# EE209_Schematic.net
KiCad netlist of a schematic drawn in Altium Designer
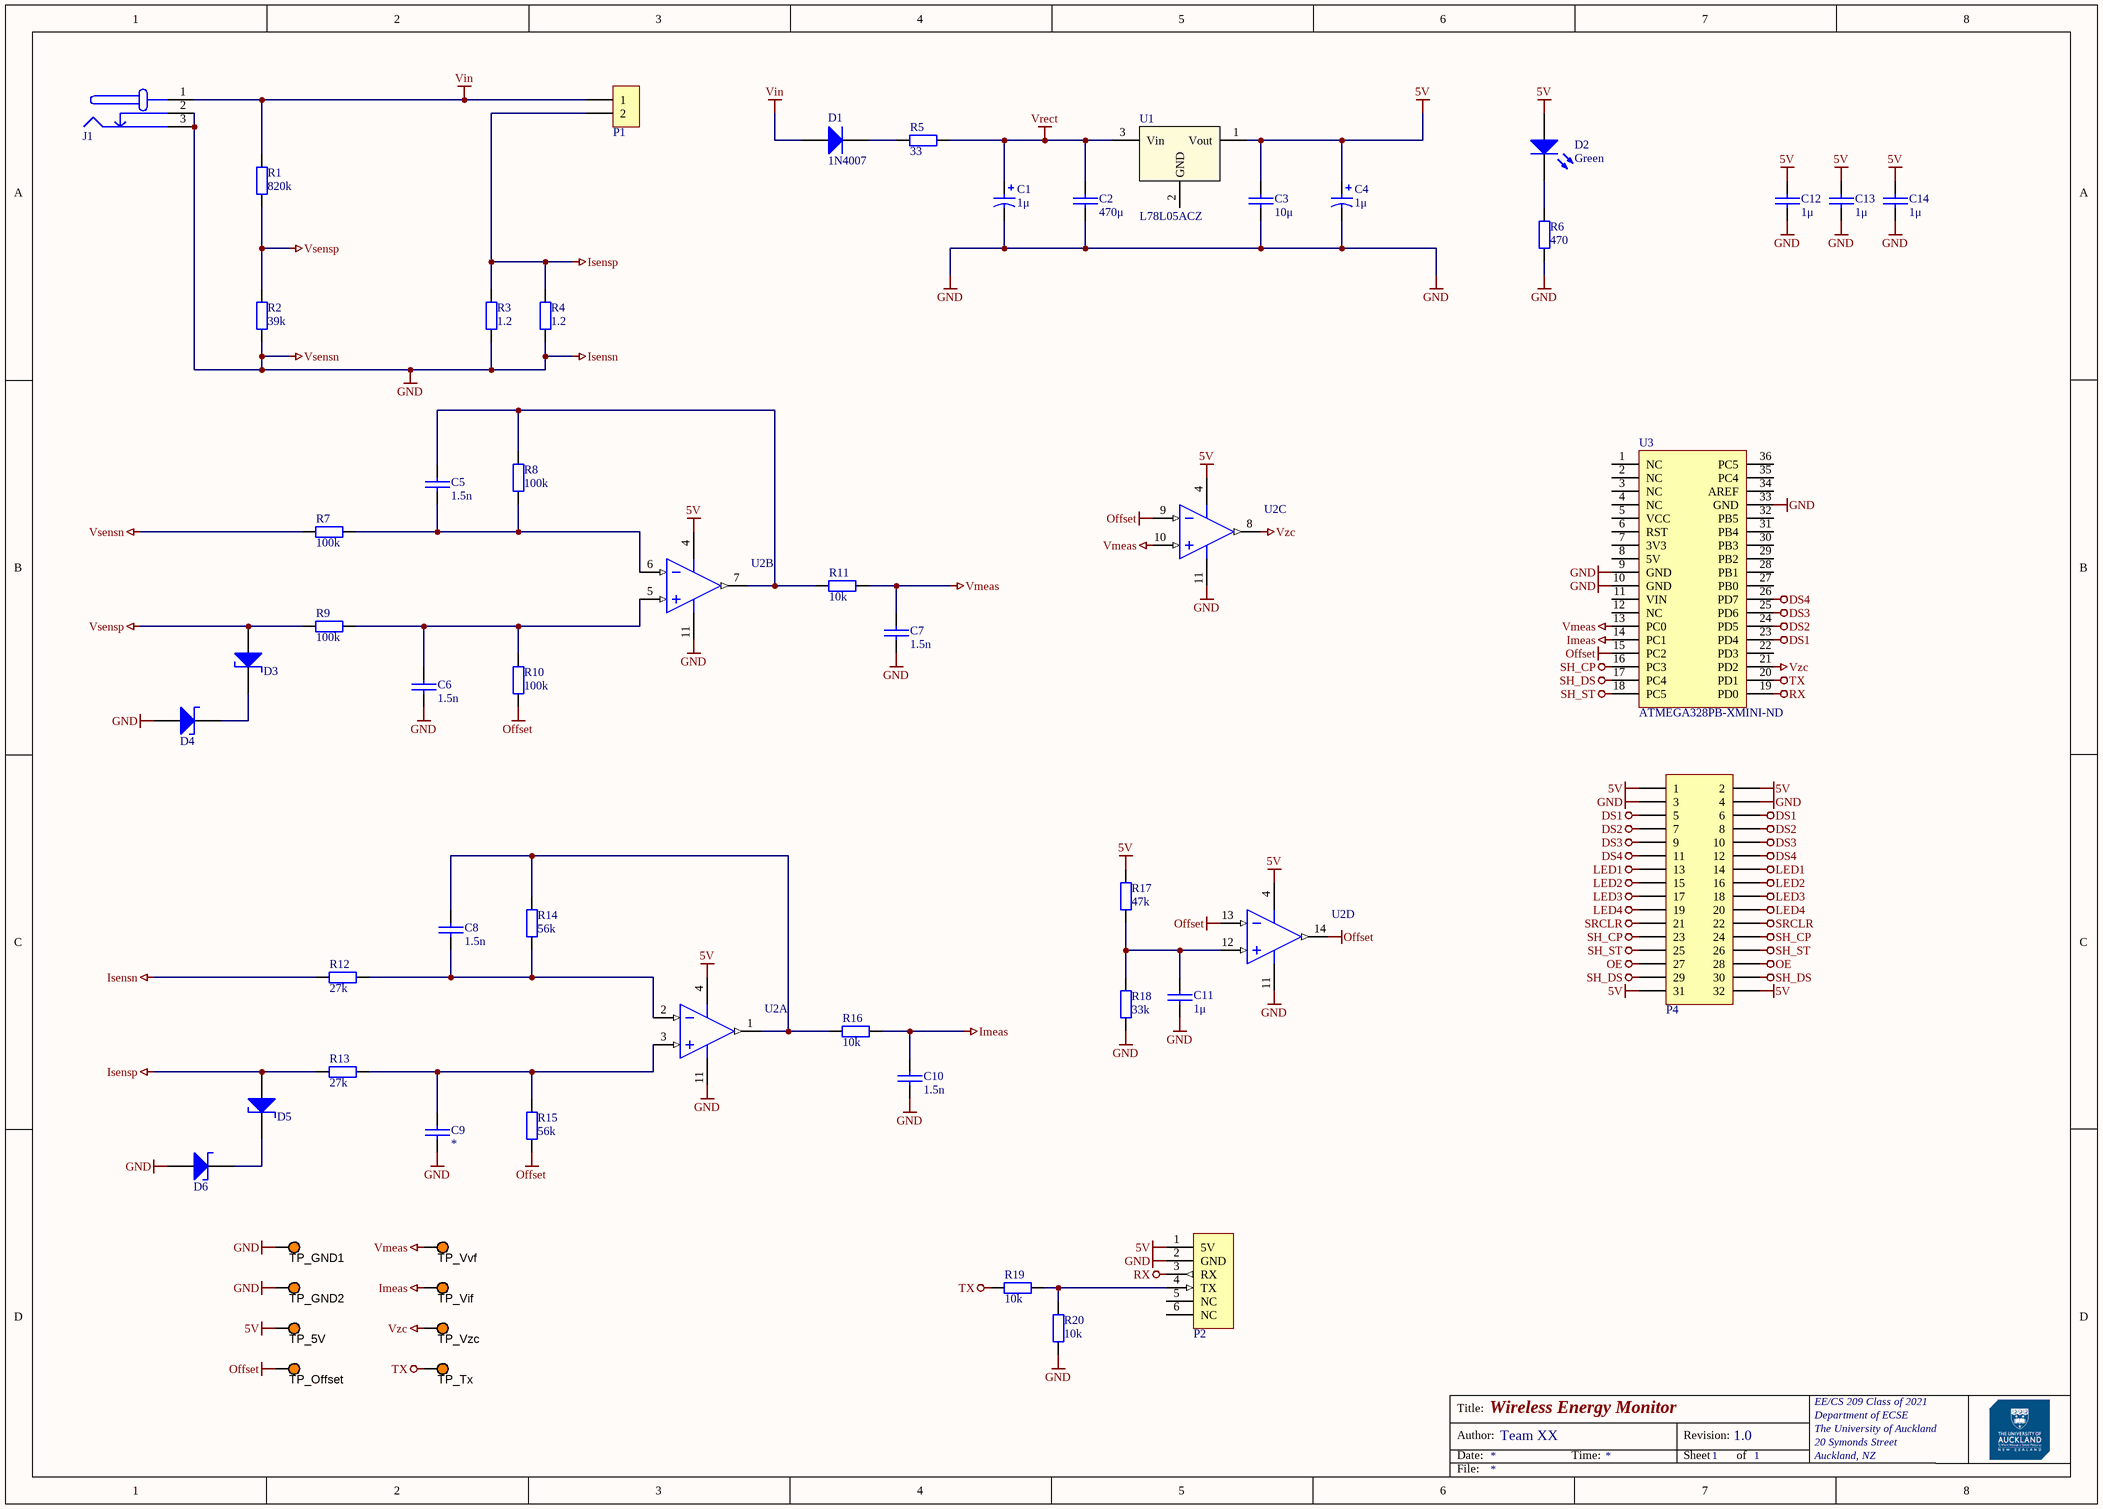
[diagram p0: EE209_Schematic.SchDoc]

(export (version "E")
  (design (tool "Eeschema 10.0.6"))
  (components
    (comp (ref "C1")
      (value "1μ")
      (footprint "CAP-RAD-2.5mm Pitch")
      (description "Electrolytic capacitor with radial package, 2mm pitch and 5.2mm diameter")
      (fields (field (name "PUBLISHER") "Altium Limited"))
      (libsource (lib "EE209_Library") (part "ElecCap_TH_2P0"))
    )
    (comp (ref "C2")
      (value "470μ")
      (footprint "CCAP-5P0")
      (description "TH ceramic capacitor with 5mm pitch")
      (libsource (lib "EE209_Library") (part "CerCap_TH_5P0"))
    )
    (comp (ref "C3")
      (value "10μ")
      (footprint "CCAP-5P0")
      (description "TH ceramic capacitor with 5mm pitch")
      (libsource (lib "EE209_Library") (part "CerCap_TH_5P0"))
    )
    (comp (ref "C4")
      (value "1μ")
      (footprint "CAP-RAD-2.5mm Pitch")
      (description "Electrolytic capacitor with radial package, 2mm pitch and 5.2mm diameter")
      (fields (field (name "PUBLISHER") "Altium Limited"))
      (libsource (lib "EE209_Library") (part "ElecCap_TH_2P0"))
    )
    (comp (ref "C5")
      (value "1.5n")
      (footprint "CCAP-5P0")
      (description "TH ceramic capacitor with 5mm pitch")
      (libsource (lib "EE209_Library") (part "CerCap_TH_5P0"))
    )
    (comp (ref "C6")
      (value "1.5n")
      (footprint "CCAP-5P0")
      (description "TH ceramic capacitor with 5mm pitch")
      (libsource (lib "EE209_Library") (part "CerCap_TH_5P0"))
    )
    (comp (ref "C7")
      (value "1.5n")
      (footprint "CCAP-5P0")
      (description "TH ceramic capacitor with 5mm pitch")
      (libsource (lib "EE209_Library") (part "CerCap_TH_5P0"))
    )
    (comp (ref "C8")
      (value "1.5n")
      (footprint "CCAP-5P0")
      (description "TH ceramic capacitor with 5mm pitch")
      (libsource (lib "EE209_Library") (part "CerCap_TH_5P0"))
    )
    (comp (ref "C9")
      (value "*")
      (footprint "CCAP-5P0")
      (description "TH ceramic capacitor with 5mm pitch")
      (libsource (lib "EE209_Library") (part "CerCap_TH_5P0"))
    )
    (comp (ref "C10")
      (value "1.5n")
      (footprint "CCAP-5P0")
      (description "TH ceramic capacitor with 5mm pitch")
      (libsource (lib "EE209_Library") (part "CerCap_TH_5P0"))
    )
    (comp (ref "C11")
      (value "1μ")
      (footprint "CCAP-5P0")
      (description "TH ceramic capacitor with 5mm pitch")
      (libsource (lib "EE209_Library") (part "CerCap_TH_5P0"))
    )
    (comp (ref "C12")
      (value "1μ")
      (footprint "CCAP-5P0")
      (description "TH ceramic capacitor with 5mm pitch")
      (libsource (lib "EE209_Library") (part "CerCap_TH_5P0"))
    )
    (comp (ref "C13")
      (value "1μ")
      (footprint "CCAP-5P0")
      (description "TH ceramic capacitor with 5mm pitch")
      (libsource (lib "EE209_Library") (part "CerCap_TH_5P0"))
    )
    (comp (ref "C14")
      (value "1μ")
      (footprint "CCAP-5P0")
      (description "TH ceramic capacitor with 5mm pitch")
      (libsource (lib "EE209_Library") (part "CerCap_TH_5P0"))
    )
    (comp (ref "D1")
      (value "1N4007")
      (footprint "1N4007-MFG")
      (description "1N4007 1000V standard axial diode")
      (libsource (lib "EE209_Library") (part "1N4007_TH_4AX0"))
    )
    (comp (ref "D2")
      (value "Green")
      (footprint "LED")
      (description "Typical throughole GaAs LED with 2.54mm pitch")
      (fields (field (name "MANUFACTURER") "Generic Components") (field (name "PUBLISHER") "Altium Limited"))
      (libsource (lib "EE209_Library") (part "LED_TH_2P54"))
    )
    (comp (ref "D3")
      (value "BZX79-CXVX")
      (footprint "AXIAL-Zener-0.4")
      (description "Axial zener diode BZX79 series")
      (fields
        (field (name "MANUFACTURER") "Nexperia USA Inc.")
        (field (name "MANUFACTURER PART NUMBER") "BZX79-C4V7,143")
      )
      (libsource (lib "EE209_Library") (part "Zener_TH_4AX0"))
    )
    (comp (ref "D4")
      (value "BZX79-CXVX")
      (footprint "AXIAL-Zener-0.4")
      (description "Axial zener diode BZX79 series")
      (fields
        (field (name "MANUFACTURER") "Nexperia USA Inc.")
        (field (name "MANUFACTURER PART NUMBER") "BZX79-C4V7,143")
      )
      (libsource (lib "EE209_Library") (part "Zener_TH_4AX0"))
    )
    (comp (ref "D5")
      (value "BZX79-CXVX")
      (footprint "AXIAL-Zener-0.4")
      (description "Axial zener diode BZX79 series")
      (fields
        (field (name "MANUFACTURER") "Nexperia USA Inc.")
        (field (name "MANUFACTURER PART NUMBER") "BZX79-C4V7,143")
      )
      (libsource (lib "EE209_Library") (part "Zener_TH_4AX0"))
    )
    (comp (ref "D6")
      (value "BZX79-CXVX")
      (footprint "AXIAL-Zener-0.4")
      (description "Axial zener diode BZX79 series")
      (fields
        (field (name "MANUFACTURER") "Nexperia USA Inc.")
        (field (name "MANUFACTURER PART NUMBER") "BZX79-C4V7,143")
      )
      (libsource (lib "EE209_Library") (part "Zener_TH_4AX0"))
    )
    (comp (ref "J1")
      (value "DC barrel jack")
      (footprint "AC-Socket")
      (description "DC barrel jack connection to AC source")
      (libsource (lib "EE209_Library") (part "AC_Input"))
    )
    (comp (ref "P1")
      (value "Dual Banana Plugs")
      (footprint "Dual Banana Plug")
      (description "Dual banana plugs connection to the AC load")
      (fields (field (name "PUBLISHER") "Altium Limited"))
      (libsource (lib "EE209_Library") (part "AC_Output"))
    )
    (comp (ref "P2")
      (value "BLE Module Header")
      (footprint "HM10_HDR1X6")
      (description "2.54mm pitch 6-pin header for BLE module")
      (fields (field (name "PUBLISHER") "Altium Limited"))
      (libsource (lib "EE209_Library") (part "BLEModule_TH"))
    )
    (comp (ref "P4")
      (value "Display")
      (footprint "Display")
      (description "16-Pin Header Connecting Display")
      (libsource (lib "EE209_Library") (part "Display"))
    )
    (comp (ref "R1")
      (value "820k")
      (footprint "AXIAL-0.4")
      (description "Through hole resistor")
      (fields (field (name "PUBLISHER") "Altium Limited"))
      (libsource (lib "EE209_Library") (part "Res_TH_0AX4"))
    )
    (comp (ref "R2")
      (value "39k")
      (footprint "AXIAL-0.4")
      (description "Through hole resistor")
      (fields (field (name "PUBLISHER") "Altium Limited"))
      (libsource (lib "EE209_Library") (part "Res_TH_0AX4"))
    )
    (comp (ref "R3")
      (value "1.2")
      (footprint "AXIAL-0.4")
      (description "Through hole resistor")
      (fields (field (name "PUBLISHER") "Altium Limited"))
      (libsource (lib "EE209_Library") (part "Res_TH_0AX4"))
    )
    (comp (ref "R4")
      (value "1.2")
      (footprint "AXIAL-0.4")
      (description "Through hole resistor")
      (fields (field (name "PUBLISHER") "Altium Limited"))
      (libsource (lib "EE209_Library") (part "Res_TH_0AX4"))
    )
    (comp (ref "R5")
      (value "33")
      (footprint "AXIAL-0.4")
      (description "Through hole resistor")
      (fields (field (name "PUBLISHER") "Altium Limited"))
      (libsource (lib "") (part "Res_TH_0AX4_1"))
    )
    (comp (ref "R6")
      (value "470")
      (footprint "AXIAL-0.4")
      (description "Through hole resistor")
      (fields (field (name "PUBLISHER") "Altium Limited"))
      (libsource (lib "EE209_Library") (part "Res_TH_0AX4"))
    )
    (comp (ref "R7")
      (value "100k")
      (footprint "AXIAL-0.4")
      (description "Through hole resistor")
      (fields (field (name "PUBLISHER") "Altium Limited"))
      (libsource (lib "") (part "Res_TH_0AX4_1"))
    )
    (comp (ref "R8")
      (value "100k")
      (footprint "AXIAL-0.4")
      (description "Through hole resistor")
      (fields (field (name "PUBLISHER") "Altium Limited"))
      (libsource (lib "EE209_Library") (part "Res_TH_0AX4"))
    )
    (comp (ref "R9")
      (value "100k")
      (footprint "AXIAL-0.4")
      (description "Through hole resistor")
      (fields (field (name "PUBLISHER") "Altium Limited"))
      (libsource (lib "") (part "Res_TH_0AX4_1"))
    )
    (comp (ref "R10")
      (value "100k")
      (footprint "AXIAL-0.4")
      (description "Through hole resistor")
      (fields (field (name "PUBLISHER") "Altium Limited"))
      (libsource (lib "EE209_Library") (part "Res_TH_0AX4"))
    )
    (comp (ref "R11")
      (value "10k")
      (footprint "AXIAL-0.4")
      (description "Through hole resistor")
      (fields (field (name "PUBLISHER") "Altium Limited"))
      (libsource (lib "") (part "Res_TH_0AX4_1"))
    )
    (comp (ref "R12")
      (value "27k")
      (footprint "AXIAL-0.4")
      (description "Through hole resistor")
      (fields (field (name "PUBLISHER") "Altium Limited"))
      (libsource (lib "") (part "Res_TH_0AX4_1"))
    )
    (comp (ref "R13")
      (value "27k")
      (footprint "AXIAL-0.4")
      (description "Through hole resistor")
      (fields (field (name "PUBLISHER") "Altium Limited"))
      (libsource (lib "") (part "Res_TH_0AX4_1"))
    )
    (comp (ref "R14")
      (value "56k")
      (footprint "AXIAL-0.4")
      (description "Through hole resistor")
      (fields (field (name "PUBLISHER") "Altium Limited"))
      (libsource (lib "EE209_Library") (part "Res_TH_0AX4"))
    )
    (comp (ref "R15")
      (value "56k")
      (footprint "AXIAL-0.4")
      (description "Through hole resistor")
      (fields (field (name "PUBLISHER") "Altium Limited"))
      (libsource (lib "EE209_Library") (part "Res_TH_0AX4"))
    )
    (comp (ref "R16")
      (value "10k")
      (footprint "AXIAL-0.4")
      (description "Through hole resistor")
      (fields (field (name "PUBLISHER") "Altium Limited"))
      (libsource (lib "") (part "Res_TH_0AX4_1"))
    )
    (comp (ref "R17")
      (value "47k")
      (footprint "AXIAL-0.4")
      (description "Through hole resistor")
      (fields (field (name "PUBLISHER") "Altium Limited"))
      (libsource (lib "EE209_Library") (part "Res_TH_0AX4"))
    )
    (comp (ref "R18")
      (value "33k")
      (footprint "AXIAL-0.4")
      (description "Through hole resistor")
      (fields (field (name "PUBLISHER") "Altium Limited"))
      (libsource (lib "EE209_Library") (part "Res_TH_0AX4"))
    )
    (comp (ref "R19")
      (value "10k")
      (footprint "AXIAL-0.4")
      (description "Through hole resistor")
      (fields (field (name "PUBLISHER") "Altium Limited"))
      (libsource (lib "") (part "Res_TH_0AX4_2"))
    )
    (comp (ref "R20")
      (value "10k")
      (footprint "AXIAL-0.4")
      (description "Through hole resistor")
      (fields (field (name "PUBLISHER") "Altium Limited"))
      (libsource (lib "EE209_Library") (part "Res_TH_0AX4"))
    )
    (comp (ref "TP_5V")
      (value "5003")
      (footprint "TP_TH")
      (description "Test Point, Orange, 1-Pin THD, RoHS")
      (libsource (lib "EE209_Library") (part "TestPoint"))
    )
    (comp (ref "TP_GND1")
      (value "5003")
      (footprint "TP_TH")
      (description "Test Point, Orange, 1-Pin THD, RoHS")
      (libsource (lib "EE209_Library") (part "TestPoint"))
    )
    (comp (ref "TP_GND2")
      (value "5003")
      (footprint "TP_TH")
      (description "Test Point, Orange, 1-Pin THD, RoHS")
      (libsource (lib "EE209_Library") (part "TestPoint"))
    )
    (comp (ref "TP_Offset")
      (value "5003")
      (footprint "TP_TH")
      (description "Test Point, Orange, 1-Pin THD, RoHS")
      (libsource (lib "EE209_Library") (part "TestPoint"))
    )
    (comp (ref "TP_Tx")
      (value "5003")
      (footprint "TP_TH")
      (description "Test Point, Orange, 1-Pin THD, RoHS")
      (libsource (lib "EE209_Library") (part "TestPoint"))
    )
    (comp (ref "TP_Vif")
      (value "5003")
      (footprint "TP_TH")
      (description "Test Point, Orange, 1-Pin THD, RoHS")
      (libsource (lib "EE209_Library") (part "TestPoint"))
    )
    (comp (ref "TP_Vvf")
      (value "5003")
      (footprint "TP_TH")
      (description "Test Point, Orange, 1-Pin THD, RoHS")
      (libsource (lib "EE209_Library") (part "TestPoint"))
    )
    (comp (ref "TP_Vzc")
      (value "5003")
      (footprint "TP_TH")
      (description "Test Point, Orange, 1-Pin THD, RoHS")
      (libsource (lib "EE209_Library") (part "TestPoint"))
    )
    (comp (ref "U1")
      (value "L78L05ACZ")
      (footprint "TO-92")
      (description "Voltage Regulator 5V")
      (fields
        (field (name "MANUFACTURER") "ON Semiconductor")
        (field (name "MANUFACTURER PART NUMBER") "LM78L05ACZX")
      )
      (libsource (lib "EE209_Library") (part "L78L05_TH_TO92"))
    )
    (comp (ref "U2")
      (value "LM324")
      (footprint "DIP-14")
      (description "IC OPAMP GP 14DIP")
      (fields
        (field (name "MANUFACTURER") "ON Semiconductor")
        (field (name "MANUFACTURER PART NUMBER") "LM324N")
      )
      (libsource (lib "EE209_Library") (part "LM324N_TH_DIP16"))
    )
    (comp (ref "U3")
      (value "ATmega328PB Xplained Mini Header")
      (footprint "ATmeg328P Xplained")
      (description "Dual 18-pin headers connecting to ATmega328PB Xplained Mini")
      (fields
        (field (name "MANUFACTURER") "Microchip Technology")
        (field (name "MANUFACTURER PART NUMBER") "ATMEGA328PB-XMINI")
        (field (name "SUPPLIER PART NUMBER 1") "ATMEGA328PB-XMINI-ND")
      )
      (libsource (lib "EE209_Library") (part "ATmega328PBXplained_TH"))
    )
  )
  (nets
    (net (code "1") (name "5V") (class "Default")
      (node (ref "C12") (pin "1") (pinfunction "1_1") (pintype "passive"))
      (node (ref "C13") (pin "1") (pinfunction "1_1") (pintype "passive"))
      (node (ref "C14") (pin "1") (pinfunction "1_1") (pintype "passive"))
      (node (ref "C3") (pin "1") (pinfunction "1_1") (pintype "passive"))
      (node (ref "C4") (pin "1") (pinfunction "1_1") (pintype "passive"))
      (node (ref "D2") (pin "1") (pinfunction "A_1") (pintype "passive"))
      (node (ref "P2") (pin "1") (pinfunction "5V_1") (pintype "passive"))
      (node (ref "P4") (pin "1") (pinfunction "1_1") (pintype "passive"))
      (node (ref "P4") (pin "2") (pinfunction "2_2") (pintype "passive"))
      (node (ref "P4") (pin "31") (pinfunction "31_31") (pintype "passive"))
      (node (ref "P4") (pin "32") (pinfunction "32_32") (pintype "passive"))
      (node (ref "R17") (pin "2") (pinfunction "2_2") (pintype "passive"))
      (node (ref "TP_5V") (pin "1") (pinfunction "1_1") (pintype "passive"))
      (node (ref "U1") (pin "1") (pinfunction "Vout_1") (pintype "passive"))
      (node (ref "U2") (pin "4") (pinfunction "VDD_4") (pintype "power_in"))
    )
    (net (code "2") (name "DS1") (class "Default")
      (node (ref "P4") (pin "5") (pinfunction "5_5") (pintype "passive"))
      (node (ref "P4") (pin "6") (pinfunction "6_6") (pintype "passive"))
      (node (ref "U3") (pin "23") (pinfunction "PD4_23") (pintype "passive"))
    )
    (net (code "3") (name "DS2") (class "Default")
      (node (ref "P4") (pin "7") (pinfunction "7_7") (pintype "passive"))
      (node (ref "P4") (pin "8") (pinfunction "8_8") (pintype "passive"))
      (node (ref "U3") (pin "24") (pinfunction "PD5_24") (pintype "passive"))
    )
    (net (code "4") (name "DS3") (class "Default")
      (node (ref "P4") (pin "10") (pinfunction "10_10") (pintype "passive"))
      (node (ref "P4") (pin "9") (pinfunction "9_9") (pintype "passive"))
      (node (ref "U3") (pin "25") (pinfunction "PD6_25") (pintype "passive"))
    )
    (net (code "5") (name "DS4") (class "Default")
      (node (ref "P4") (pin "11") (pinfunction "11_11") (pintype "passive"))
      (node (ref "P4") (pin "12") (pinfunction "12_12") (pintype "passive"))
      (node (ref "U3") (pin "26") (pinfunction "PD7_26") (pintype "passive"))
    )
    (net (code "6") (name "GND") (class "Default")
      (node (ref "C1") (pin "2") (pinfunction "2_2") (pintype "passive"))
      (node (ref "C10") (pin "2") (pinfunction "2_2") (pintype "passive"))
      (node (ref "C11") (pin "1") (pinfunction "1_1") (pintype "passive"))
      (node (ref "C12") (pin "2") (pinfunction "2_2") (pintype "passive"))
      (node (ref "C13") (pin "2") (pinfunction "2_2") (pintype "passive"))
      (node (ref "C14") (pin "2") (pinfunction "2_2") (pintype "passive"))
      (node (ref "C2") (pin "2") (pinfunction "2_2") (pintype "passive"))
      (node (ref "C3") (pin "2") (pinfunction "2_2") (pintype "passive"))
      (node (ref "C4") (pin "2") (pinfunction "2_2") (pintype "passive"))
      (node (ref "C6") (pin "2") (pinfunction "2_2") (pintype "passive"))
      (node (ref "C7") (pin "2") (pinfunction "2_2") (pintype "passive"))
      (node (ref "C9") (pin "2") (pinfunction "2_2") (pintype "passive"))
      (node (ref "D4") (pin "1") (pinfunction "A_1") (pintype "passive"))
      (node (ref "D6") (pin "1") (pinfunction "A_1") (pintype "passive"))
      (node (ref "J1") (pin "2") (pinfunction "GND_ALT_2") (pintype "power_in"))
      (node (ref "J1") (pin "3") (pinfunction "GND_3") (pintype "power_in"))
      (node (ref "P2") (pin "2") (pinfunction "GND_2") (pintype "passive"))
      (node (ref "P4") (pin "3") (pinfunction "3_3") (pintype "passive"))
      (node (ref "P4") (pin "4") (pinfunction "4_4") (pintype "passive"))
      (node (ref "R12") (pin "1") (pinfunction "1_1") (pintype "passive"))
      (node (ref "R18") (pin "1") (pinfunction "1_1") (pintype "passive"))
      (node (ref "R2") (pin "1") (pinfunction "1_1") (pintype "passive"))
      (node (ref "R20") (pin "1") (pinfunction "1_1") (pintype "passive"))
      (node (ref "R3") (pin "1") (pinfunction "1_1") (pintype "passive"))
      (node (ref "R4") (pin "1") (pinfunction "1_1") (pintype "passive"))
      (node (ref "R6") (pin "1") (pinfunction "1_1") (pintype "passive"))
      (node (ref "R7") (pin "1") (pinfunction "1_1") (pintype "passive"))
      (node (ref "TP_GND1") (pin "1") (pinfunction "1_1") (pintype "passive"))
      (node (ref "TP_GND2") (pin "1") (pinfunction "1_1") (pintype "passive"))
      (node (ref "U2") (pin "11") (pinfunction "VSS_11") (pintype "power_in"))
      (node (ref "U3") (pin "10") (pinfunction "GND_10") (pintype "power_in"))
      (node (ref "U3") (pin "33") (pinfunction "GND_33") (pintype "passive"))
      (node (ref "U3") (pin "9") (pinfunction "GND_9") (pintype "power_in"))
    )
    (net (code "7") (name "Imeas") (class "Default")
      (node (ref "C10") (pin "1") (pinfunction "1_1") (pintype "passive"))
      (node (ref "R16") (pin "2") (pinfunction "2_2") (pintype "passive"))
      (node (ref "TP_Vif") (pin "1") (pinfunction "1_1") (pintype "passive"))
      (node (ref "U3") (pin "14") (pinfunction "PC1_14") (pintype "passive"))
    )
    (net (code "8") (name "Isensp") (class "Default")
      (node (ref "D5") (pin "1") (pinfunction "A_1") (pintype "passive"))
      (node (ref "P1") (pin "2") (pinfunction "2_2") (pintype "passive"))
      (node (ref "R13") (pin "1") (pinfunction "1_1") (pintype "passive"))
      (node (ref "R3") (pin "2") (pinfunction "2_2") (pintype "passive"))
      (node (ref "R4") (pin "2") (pinfunction "2_2") (pintype "passive"))
    )
    (net (code "9") (name "LED1") (class "Default")
      (node (ref "P4") (pin "13") (pinfunction "13_13") (pintype "passive"))
      (node (ref "P4") (pin "14") (pinfunction "14_14") (pintype "passive"))
    )
    (net (code "10") (name "LED2") (class "Default")
      (node (ref "P4") (pin "15") (pinfunction "15_15") (pintype "passive"))
      (node (ref "P4") (pin "16") (pinfunction "16_16") (pintype "passive"))
    )
    (net (code "11") (name "LED3") (class "Default")
      (node (ref "P4") (pin "17") (pinfunction "17_17") (pintype "passive"))
      (node (ref "P4") (pin "18") (pinfunction "18_18") (pintype "passive"))
    )
    (net (code "12") (name "LED4") (class "Default")
      (node (ref "P4") (pin "19") (pinfunction "19_19") (pintype "passive"))
      (node (ref "P4") (pin "20") (pinfunction "20_20") (pintype "passive"))
    )
    (net (code "13") (name "Net-(D1-K)") (class "Default")
      (node (ref "D1") (pin "2") (pinfunction "K_2") (pintype "passive"))
      (node (ref "R5") (pin "1") (pinfunction "1_1") (pintype "passive"))
    )
    (net (code "14") (name "Net-(D2-K)") (class "Default")
      (node (ref "D2") (pin "2") (pinfunction "K_2") (pintype "passive"))
      (node (ref "R6") (pin "2") (pinfunction "2_2") (pintype "passive"))
    )
    (net (code "15") (name "Net-(D3-K)") (class "Default")
      (node (ref "D3") (pin "2") (pinfunction "K_2") (pintype "passive"))
      (node (ref "D4") (pin "2") (pinfunction "K_2") (pintype "passive"))
    )
    (net (code "16") (name "Net-(D5-K)") (class "Default")
      (node (ref "D5") (pin "2") (pinfunction "K_2") (pintype "passive"))
      (node (ref "D6") (pin "2") (pinfunction "K_2") (pintype "passive"))
    )
    (net (code "17") (name "Net-(P2-TX)") (class "Default")
      (node (ref "P2") (pin "4") (pinfunction "TX_4") (pintype "input"))
      (node (ref "R19") (pin "1") (pinfunction "1_1") (pintype "passive"))
      (node (ref "R20") (pin "2") (pinfunction "2_2") (pintype "passive"))
    )
    (net (code "18") (name "Net-(U2A-VINA+)") (class "Default")
      (node (ref "C9") (pin "1") (pinfunction "1_1") (pintype "passive"))
      (node (ref "R13") (pin "2") (pinfunction "2_2") (pintype "passive"))
      (node (ref "R15") (pin "2") (pinfunction "2_2") (pintype "passive"))
      (node (ref "U2") (pin "3") (pinfunction "VINA+_3") (pintype "input"))
    )
    (net (code "19") (name "Net-(U2A-VINA-)") (class "Default")
      (node (ref "C8") (pin "2") (pinfunction "2_2") (pintype "passive"))
      (node (ref "R12") (pin "2") (pinfunction "2_2") (pintype "passive"))
      (node (ref "R14") (pin "1") (pinfunction "1_1") (pintype "passive"))
      (node (ref "U2") (pin "2") (pinfunction "VINA-_2") (pintype "input"))
    )
    (net (code "20") (name "Net-(U2A-VOUTA)") (class "Default")
      (node (ref "C8") (pin "1") (pinfunction "1_1") (pintype "passive"))
      (node (ref "R14") (pin "2") (pinfunction "2_2") (pintype "passive"))
      (node (ref "R16") (pin "1") (pinfunction "1_1") (pintype "passive"))
      (node (ref "U2") (pin "1") (pinfunction "VOUTA_1") (pintype "output"))
    )
    (net (code "21") (name "Net-(U2B-VINB+)") (class "Default")
      (node (ref "C6") (pin "1") (pinfunction "1_1") (pintype "passive"))
      (node (ref "R10") (pin "2") (pinfunction "2_2") (pintype "passive"))
      (node (ref "R9") (pin "2") (pinfunction "2_2") (pintype "passive"))
      (node (ref "U2") (pin "5") (pinfunction "VINB+_5") (pintype "input"))
    )
    (net (code "22") (name "Net-(U2B-VINB-)") (class "Default")
      (node (ref "C5") (pin "2") (pinfunction "2_2") (pintype "passive"))
      (node (ref "R7") (pin "2") (pinfunction "2_2") (pintype "passive"))
      (node (ref "R8") (pin "1") (pinfunction "1_1") (pintype "passive"))
      (node (ref "U2") (pin "6") (pinfunction "VINB-_6") (pintype "input"))
    )
    (net (code "23") (name "Net-(U2B-VOUTB)") (class "Default")
      (node (ref "C5") (pin "1") (pinfunction "1_1") (pintype "passive"))
      (node (ref "R11") (pin "1") (pinfunction "1_1") (pintype "passive"))
      (node (ref "R8") (pin "2") (pinfunction "2_2") (pintype "passive"))
      (node (ref "U2") (pin "7") (pinfunction "VOUTB_7") (pintype "output"))
    )
    (net (code "24") (name "Net-(U2D-VIND+)") (class "Default")
      (node (ref "C11") (pin "2") (pinfunction "2_2") (pintype "passive"))
      (node (ref "R17") (pin "1") (pinfunction "1_1") (pintype "passive"))
      (node (ref "R18") (pin "2") (pinfunction "2_2") (pintype "passive"))
      (node (ref "U2") (pin "12") (pinfunction "VIND+_12") (pintype "input"))
    )
    (net (code "25") (name "OE") (class "Default")
      (node (ref "P4") (pin "27") (pinfunction "27_27") (pintype "passive"))
      (node (ref "P4") (pin "28") (pinfunction "28_28") (pintype "passive"))
    )
    (net (code "26") (name "Offset") (class "Default")
      (node (ref "R10") (pin "1") (pinfunction "1_1") (pintype "passive"))
      (node (ref "R15") (pin "1") (pinfunction "1_1") (pintype "passive"))
      (node (ref "TP_Offset") (pin "1") (pinfunction "1_1") (pintype "passive"))
      (node (ref "U2") (pin "13") (pinfunction "VIND-_13") (pintype "input"))
      (node (ref "U2") (pin "14") (pinfunction "VOUTD_14") (pintype "output"))
      (node (ref "U2") (pin "9") (pinfunction "VINC-_9") (pintype "input"))
      (node (ref "U3") (pin "15") (pinfunction "PC2_15") (pintype "passive"))
    )
    (net (code "27") (name "RX") (class "Default")
      (node (ref "P2") (pin "3") (pinfunction "RX_3") (pintype "output"))
      (node (ref "U3") (pin "19") (pinfunction "PD0_19") (pintype "passive"))
    )
    (net (code "28") (name "SH_CP") (class "Default")
      (node (ref "P4") (pin "23") (pinfunction "23_23") (pintype "passive"))
      (node (ref "P4") (pin "24") (pinfunction "24_24") (pintype "passive"))
      (node (ref "U3") (pin "16") (pinfunction "PC3_16") (pintype "passive"))
    )
    (net (code "29") (name "SH_DS") (class "Default")
      (node (ref "P4") (pin "29") (pinfunction "29_29") (pintype "passive"))
      (node (ref "P4") (pin "30") (pinfunction "30_30") (pintype "passive"))
      (node (ref "U3") (pin "17") (pinfunction "PC4_17") (pintype "passive"))
    )
    (net (code "30") (name "SH_ST") (class "Default")
      (node (ref "P4") (pin "25") (pinfunction "25_25") (pintype "passive"))
      (node (ref "P4") (pin "26") (pinfunction "26_26") (pintype "passive"))
      (node (ref "U3") (pin "18") (pinfunction "PC5_18") (pintype "passive"))
    )
    (net (code "31") (name "SRCLR") (class "Default")
      (node (ref "P4") (pin "21") (pinfunction "21_21") (pintype "passive"))
      (node (ref "P4") (pin "22") (pinfunction "22_22") (pintype "passive"))
    )
    (net (code "32") (name "TX") (class "Default")
      (node (ref "R19") (pin "2") (pinfunction "2_2") (pintype "passive"))
      (node (ref "TP_Tx") (pin "1") (pinfunction "1_1") (pintype "passive"))
      (node (ref "U3") (pin "20") (pinfunction "PD1_20") (pintype "passive"))
    )
    (net (code "33") (name "Vin") (class "Default")
      (node (ref "D1") (pin "1") (pinfunction "A_1") (pintype "passive"))
      (node (ref "J1") (pin "1") (pinfunction "VCC_1") (pintype "power_in"))
      (node (ref "P1") (pin "1") (pinfunction "1_1") (pintype "passive"))
      (node (ref "R1") (pin "2") (pinfunction "2_2") (pintype "passive"))
    )
    (net (code "34") (name "Vmeas") (class "Default")
      (node (ref "C7") (pin "1") (pinfunction "1_1") (pintype "passive"))
      (node (ref "R11") (pin "2") (pinfunction "2_2") (pintype "passive"))
      (node (ref "TP_Vvf") (pin "1") (pinfunction "1_1") (pintype "passive"))
      (node (ref "U2") (pin "10") (pinfunction "VINC+_10") (pintype "input"))
      (node (ref "U3") (pin "13") (pinfunction "PC0_13") (pintype "passive"))
    )
    (net (code "35") (name "Vrect") (class "Default")
      (node (ref "C1") (pin "1") (pinfunction "1_1") (pintype "passive"))
      (node (ref "C2") (pin "1") (pinfunction "1_1") (pintype "passive"))
      (node (ref "R5") (pin "2") (pinfunction "2_2") (pintype "passive"))
      (node (ref "U1") (pin "3") (pinfunction "Vin_3") (pintype "passive"))
    )
    (net (code "36") (name "Vsensp") (class "Default")
      (node (ref "D3") (pin "1") (pinfunction "A_1") (pintype "passive"))
      (node (ref "R1") (pin "1") (pinfunction "1_1") (pintype "passive"))
      (node (ref "R2") (pin "2") (pinfunction "2_2") (pintype "passive"))
      (node (ref "R9") (pin "1") (pinfunction "1_1") (pintype "passive"))
    )
    (net (code "37") (name "Vzc") (class "Default")
      (node (ref "TP_Vzc") (pin "1") (pinfunction "1_1") (pintype "passive"))
      (node (ref "U2") (pin "8") (pinfunction "VOUTC_8") (pintype "output"))
      (node (ref "U3") (pin "21") (pinfunction "PD2_21") (pintype "passive"))
    )
    (net (code "38") (name "unconnected-(P2-NC-Pad5)") (class "Default")
      (node (ref "P2") (pin "5") (pinfunction "NC_5") (pintype "passive"))
    )
    (net (code "39") (name "unconnected-(P2-NC-Pad6)") (class "Default")
      (node (ref "P2") (pin "6") (pinfunction "NC_6") (pintype "passive"))
    )
    (net (code "40") (name "unconnected-(U1-GND-Pad2)") (class "Default")
      (node (ref "U1") (pin "2") (pinfunction "GND_2") (pintype "passive"))
    )
    (net (code "41") (name "unconnected-(U3-3V3-Pad7)") (class "Default")
      (node (ref "U3") (pin "7") (pinfunction "3V3_7") (pintype "passive"))
    )
    (net (code "42") (name "unconnected-(U3-5V-Pad8)") (class "Default")
      (node (ref "U3") (pin "8") (pinfunction "5V_8") (pintype "power_in"))
    )
    (net (code "43") (name "unconnected-(U3-AREF-Pad34)") (class "Default")
      (node (ref "U3") (pin "34") (pinfunction "AREF_34") (pintype "passive"))
    )
    (net (code "44") (name "unconnected-(U3-NC-Pad1)") (class "Default")
      (node (ref "U3") (pin "1") (pinfunction "NC_1") (pintype "passive"))
    )
    (net (code "45") (name "unconnected-(U3-NC-Pad2)") (class "Default")
      (node (ref "U3") (pin "2") (pinfunction "NC_2") (pintype "passive"))
    )
    (net (code "46") (name "unconnected-(U3-NC-Pad3)") (class "Default")
      (node (ref "U3") (pin "3") (pinfunction "NC_3") (pintype "passive"))
    )
    (net (code "47") (name "unconnected-(U3-NC-Pad4)") (class "Default")
      (node (ref "U3") (pin "4") (pinfunction "NC_4") (pintype "passive"))
    )
    (net (code "48") (name "unconnected-(U3-NC-Pad12)") (class "Default")
      (node (ref "U3") (pin "12") (pinfunction "NC_12") (pintype "passive"))
    )
    (net (code "49") (name "unconnected-(U3-PB0-Pad27)") (class "Default")
      (node (ref "U3") (pin "27") (pinfunction "PB0_27") (pintype "passive"))
    )
    (net (code "50") (name "unconnected-(U3-PB1-Pad28)") (class "Default")
      (node (ref "U3") (pin "28") (pinfunction "PB1_28") (pintype "passive"))
    )
    (net (code "51") (name "unconnected-(U3-PB2-Pad29)") (class "Default")
      (node (ref "U3") (pin "29") (pinfunction "PB2_29") (pintype "passive"))
    )
    (net (code "52") (name "unconnected-(U3-PB3-Pad30)") (class "Default")
      (node (ref "U3") (pin "30") (pinfunction "PB3_30") (pintype "passive"))
    )
    (net (code "53") (name "unconnected-(U3-PB4-Pad31)") (class "Default")
      (node (ref "U3") (pin "31") (pinfunction "PB4_31") (pintype "passive"))
    )
    (net (code "54") (name "unconnected-(U3-PB5-Pad32)") (class "Default")
      (node (ref "U3") (pin "32") (pinfunction "PB5_32") (pintype "passive"))
    )
    (net (code "55") (name "unconnected-(U3-PC4-Pad35)") (class "Default")
      (node (ref "U3") (pin "35") (pinfunction "PC4_35") (pintype "passive"))
    )
    (net (code "56") (name "unconnected-(U3-PC5-Pad36)") (class "Default")
      (node (ref "U3") (pin "36") (pinfunction "PC5_36") (pintype "passive"))
    )
    (net (code "57") (name "unconnected-(U3-PD3-Pad22)") (class "Default")
      (node (ref "U3") (pin "22") (pinfunction "PD3_22") (pintype "passive"))
    )
    (net (code "58") (name "unconnected-(U3-RST-Pad6)") (class "Default")
      (node (ref "U3") (pin "6") (pinfunction "RST_6") (pintype "passive"))
    )
    (net (code "59") (name "unconnected-(U3-VCC-Pad5)") (class "Default")
      (node (ref "U3") (pin "5") (pinfunction "VCC_5") (pintype "power_in"))
    )
    (net (code "60") (name "unconnected-(U3-VIN-Pad11)") (class "Default")
      (node (ref "U3") (pin "11") (pinfunction "VIN_11") (pintype "power_in"))
    )
  )
)
